# HumRigid1.net
KiCad netlist of a schematic drawn in Altium Designer
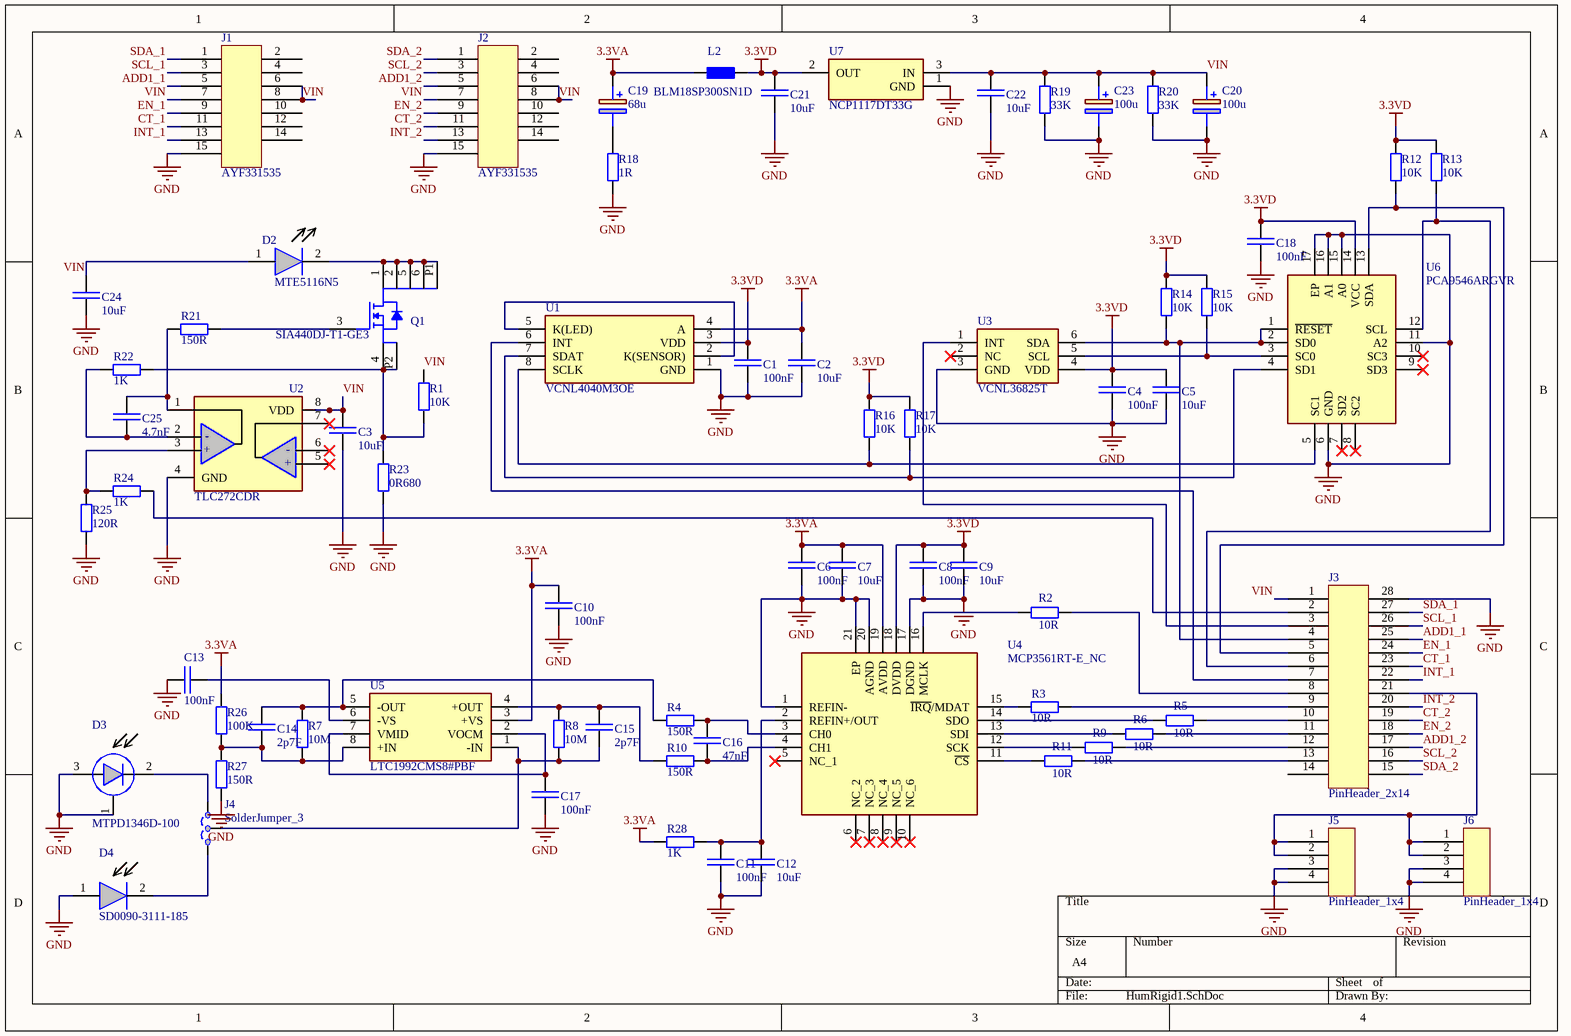
[diagram p0: HumRigid1.SchDoc]

(export (version "E")
  (design (tool "Eeschema 10.0.6"))
  (components
    (comp (ref "C1")
      (value "100nF")
      (footprint "CAP_SM0603_YAGEOCC2_N")
      (description "CAP 100nF SM0603 X7R 50V YAGEO CC2")
      (fields
        (field (name "MANUFACTURER") "Yageo")
        (field (name "MANUFACTURER PART NUMBER") "CC0603KRX7R9BB104")
      )
      (libsource (lib "symbols") (part "CC0603KRX7R9BB104"))
    )
    (comp (ref "C2")
      (value "10uF")
      (footprint "CAP_SM0805_YAGEOCC2_N")
      (description "CAP 10uF SM0805 X5R 16V YAGEO CC2")
      (fields
        (field (name "MANUFACTURER") "Yageo")
        (field (name "MANUFACTURER PART NUMBER") "CC0805KKX7R8BB225")
      )
      (libsource (lib "symbols") (part "CC0805KKX5R8BB106"))
    )
    (comp (ref "C3")
      (value "10uF")
      (footprint "CAP_SM0805_YAGEOCC2_N")
      (description "CAP 10uF SM0805 X5R 16V YAGEO CC2")
      (fields
        (field (name "MANUFACTURER") "Yageo")
        (field (name "MANUFACTURER PART NUMBER") "CC0805KKX7R8BB225")
      )
      (libsource (lib "symbols") (part "CC0805KKX5R8BB106"))
    )
    (comp (ref "C4")
      (value "100nF")
      (footprint "CAP_SM0603_YAGEOCC2_N")
      (description "CAP 100nF SM0603 X7R 50V YAGEO CC2")
      (fields
        (field (name "MANUFACTURER") "Yageo")
        (field (name "MANUFACTURER PART NUMBER") "CC0603KRX7R9BB104")
      )
      (libsource (lib "symbols") (part "CC0603KRX7R9BB104"))
    )
    (comp (ref "C5")
      (value "10uF")
      (footprint "CAP_SM0805_YAGEOCC2_N")
      (description "CAP 10uF SM0805 X5R 16V YAGEO CC2")
      (fields
        (field (name "MANUFACTURER") "Yageo")
        (field (name "MANUFACTURER PART NUMBER") "CC0805KKX7R8BB225")
      )
      (libsource (lib "symbols") (part "CC0805KKX5R8BB106"))
    )
    (comp (ref "C6")
      (value "100nF")
      (footprint "CAP_SM0603_YAGEOCC2_N")
      (description "CAP 100nF SM0603 X7R 50V YAGEO CC2")
      (fields
        (field (name "MANUFACTURER") "Yageo")
        (field (name "MANUFACTURER PART NUMBER") "CC0603KRX7R9BB104")
      )
      (libsource (lib "symbols") (part "CC0603KRX7R9BB104"))
    )
    (comp (ref "C7")
      (value "10uF")
      (footprint "CAP_SM0805_YAGEOCC2_N")
      (description "CAP 10uF SM0805 X5R 16V YAGEO CC2")
      (fields
        (field (name "MANUFACTURER") "Yageo")
        (field (name "MANUFACTURER PART NUMBER") "CC0805KKX7R8BB225")
      )
      (libsource (lib "symbols") (part "CC0805KKX5R8BB106"))
    )
    (comp (ref "C8")
      (value "100nF")
      (footprint "CAP_SM0603_YAGEOCC2_N")
      (description "CAP 100nF SM0603 X7R 50V YAGEO CC2")
      (fields
        (field (name "MANUFACTURER") "Yageo")
        (field (name "MANUFACTURER PART NUMBER") "CC0603KRX7R9BB104")
      )
      (libsource (lib "symbols") (part "CC0603KRX7R9BB104"))
    )
    (comp (ref "C9")
      (value "10uF")
      (footprint "CAP_SM0805_YAGEOCC2_N")
      (description "CAP 10uF SM0805 X5R 16V YAGEO CC2")
      (fields
        (field (name "MANUFACTURER") "Yageo")
        (field (name "MANUFACTURER PART NUMBER") "CC0805KKX7R8BB225")
      )
      (libsource (lib "symbols") (part "CC0805KKX5R8BB106"))
    )
    (comp (ref "C10")
      (value "100nF")
      (footprint "CAP_SM0603_YAGEOCC2_N")
      (description "CAP 100nF SM0603 X7R 50V YAGEO CC2")
      (fields
        (field (name "MANUFACTURER") "Yageo")
        (field (name "MANUFACTURER PART NUMBER") "CC0603KRX7R9BB104")
      )
      (libsource (lib "symbols") (part "CC0603KRX7R9BB104"))
    )
    (comp (ref "C11")
      (value "100nF")
      (footprint "CAP_SM0603_YAGEOCC2_N")
      (description "CAP 100nF SM0603 X7R 50V YAGEO CC2")
      (fields
        (field (name "MANUFACTURER") "Yageo")
        (field (name "MANUFACTURER PART NUMBER") "CC0603KRX7R9BB104")
      )
      (libsource (lib "symbols") (part "CC0603KRX7R9BB104"))
    )
    (comp (ref "C12")
      (value "10uF")
      (footprint "CAP_SM0805_YAGEOCC2_N")
      (description "CAP 10uF SM0805 X5R 16V YAGEO CC2")
      (fields
        (field (name "MANUFACTURER") "Yageo")
        (field (name "MANUFACTURER PART NUMBER") "CC0805KKX7R8BB225")
      )
      (libsource (lib "symbols") (part "CC0805KKX5R8BB106"))
    )
    (comp (ref "C13")
      (value "100nF")
      (footprint "CAP_SM0603_YAGEOCC2_N")
      (description "CAP 100nF SM0603 X7R 50V YAGEO CC2")
      (fields
        (field (name "MANUFACTURER") "Yageo")
        (field (name "MANUFACTURER PART NUMBER") "CC0603KRX7R9BB104")
      )
      (libsource (lib "symbols") (part "CC0603KRX7R9BB104"))
    )
    (comp (ref "C14")
      (value "2p7F")
      (footprint "CAP_SM0603_YAGEOCC2_N")
      (description "CAP 2.7pF (2p7F) SM0603 NPO 50V YAGEO CC2")
      (fields
        (field (name "MANUFACTURER") "Yageo")
        (field (name "MANUFACTURER PART NUMBER") "CC0603CRNPO9BN2R7")
      )
      (libsource (lib "symbols") (part "CC0603CRNPO9BN2R7"))
    )
    (comp (ref "C15")
      (value "2p7F")
      (footprint "CAP_SM0603_YAGEOCC2_N")
      (description "CAP 2.7pF (2p7F) SM0603 NPO 50V YAGEO CC2")
      (fields
        (field (name "MANUFACTURER") "Yageo")
        (field (name "MANUFACTURER PART NUMBER") "CC0603CRNPO9BN2R7")
      )
      (libsource (lib "symbols") (part "CC0603CRNPO9BN2R7"))
    )
    (comp (ref "C16")
      (value "47nF")
      (footprint "CAP_SM0603_YAGEOCC2_N")
      (description "CAP 47nF SM0603 X7R 50V YAGEO CC2")
      (fields
        (field (name "MANUFACTURER") "Yageo")
        (field (name "MANUFACTURER PART NUMBER") "CC0603KRX7R9BB223")
      )
      (libsource (lib "symbols") (part "CC0603KRX7R9BB473"))
    )
    (comp (ref "C17")
      (value "100nF")
      (footprint "CAP_SM0603_YAGEOCC2_N")
      (description "CAP 100nF SM0603 X7R 50V YAGEO CC2")
      (fields
        (field (name "MANUFACTURER") "Yageo")
        (field (name "MANUFACTURER PART NUMBER") "CC0603KRX7R9BB104")
      )
      (libsource (lib "symbols") (part "CC0603KRX7R9BB104"))
    )
    (comp (ref "C18")
      (value "100nF")
      (footprint "CAP_SM0603_YAGEOCC2_N")
      (description "CAP 100nF SM0603 X7R 50V YAGEO CC2")
      (fields
        (field (name "MANUFACTURER") "Yageo")
        (field (name "MANUFACTURER PART NUMBER") "CC0603KRX7R9BB104")
      )
      (libsource (lib "symbols") (part "CC0603KRX7R9BB104"))
    )
    (comp (ref "C19")
      (value "68u")
      (footprint "CAPAE660X770N")
      (fields
        (field (name "MOUSER PART NUMBER") "710-865080545012")
        (field (name "MANUFACTURER_PART_NUMBER") "865080545012")
      )
      (libsource (lib "symbols") (part "865080545011"))
    )
    (comp (ref "C20")
      (value "100u")
      (footprint "CAPAE660X770N")
      (fields
        (field (name "MOUSER PART NUMBER") "710-865080545012")
        (field (name "MANUFACTURER_PART_NUMBER") "865080545012")
      )
      (libsource (lib "symbols") (part "865080545012"))
    )
    (comp (ref "C21")
      (value "10uF")
      (footprint "CAP_SM0805_YAGEOCC2_N")
      (description "CAP 10uF SM0805 X5R 16V YAGEO CC2")
      (fields
        (field (name "MANUFACTURER") "Yageo")
        (field (name "MANUFACTURER PART NUMBER") "CC0805KKX7R8BB225")
      )
      (libsource (lib "symbols") (part "CC0805KKX5R8BB106"))
    )
    (comp (ref "C22")
      (value "10uF")
      (footprint "CAP_SM0805_YAGEOCC2_N")
      (description "CAP 10uF SM0805 X5R 16V YAGEO CC2")
      (fields
        (field (name "MANUFACTURER") "Yageo")
        (field (name "MANUFACTURER PART NUMBER") "CC0805KKX7R8BB225")
      )
      (libsource (lib "symbols") (part "CC0805KKX5R8BB106"))
    )
    (comp (ref "C23")
      (value "100u")
      (footprint "CAPAE660X770N")
      (fields
        (field (name "MOUSER PART NUMBER") "710-865080545012")
        (field (name "MANUFACTURER_PART_NUMBER") "865080545012")
      )
      (libsource (lib "symbols") (part "865080545012"))
    )
    (comp (ref "C24")
      (value "10uF")
      (footprint "CAP_SM0805_YAGEOCC2_N")
      (description "CAP 10uF SM0805 X5R 16V YAGEO CC2")
      (fields
        (field (name "MANUFACTURER") "Yageo")
        (field (name "MANUFACTURER PART NUMBER") "CC0805KKX7R8BB225")
      )
      (libsource (lib "symbols") (part "CC0805KKX5R8BB106"))
    )
    (comp (ref "C25")
      (value "4.7nF")
      (footprint "CAP_SM0603_YAGEOCC2_N")
      (description "CAP 4.7nF SM0603 X7R 50V YAGEO CC2")
      (fields
        (field (name "MANUFACTURER") "Yageo")
        (field (name "MANUFACTURER PART NUMBER") "CC0603KRX7R9BB223")
      )
      (libsource (lib "symbols") (part "CC0603KRX7R9BB472"))
    )
    (comp (ref "D2")
      (value "MTE5116N5")
      (footprint "MTE5116N5")
      (description "MTE5116N5 SWIR Infrared Emitter 1650nm")
      (libsource (lib "symbols") (part "MTE5116N5"))
    )
    (comp (ref "D3")
      (value "MTPD1346D-100")
      (footprint "MTPD1346D100")
      (description "MTPD1346D-100 High Speed InGaAs PIN Photodiode 600-1750nm")
      (libsource (lib "symbols") (part "MTPD1346D-100"))
    )
    (comp (ref "D4")
      (value "SD0090-3111-185")
      (footprint "SD00903111185")
      (description "SD0090-3111-185 SMD InGaAs Photodiode 900-1650nm")
      (libsource (lib "symbols") (part "SD0090-3111-185"))
    )
    (comp (ref "J1")
      (value "AYF331535")
      (footprint "AYF331535")
      (description "AYF331535 FFC & FPC-Steckverbinder CONNECTOR SURFACE MOUNT")
      (libsource (lib "Base_Symbols") (part "AYF331535"))
    )
    (comp (ref "J2")
      (value "AYF331535")
      (footprint "AYF331535")
      (description "AYF331535 FFC & FPC-Steckverbinder CONNECTOR SURFACE MOUNT")
      (libsource (lib "Base_Symbols") (part "AYF331535"))
    )
    (comp (ref "J3")
      (value "PinHeader_2x14")
      (footprint "PinHeader_2x14_2.54mm")
      (description "PinHeader_2x14 2.54mm Pitch")
      (libsource (lib "symbols") (part "PinHeader_2x14_2.54mm_1"))
    )
    (comp (ref "J4")
      (value "SolderJumper_3")
      (footprint "SolderJumper3_1")
      (libsource (lib "symbols") (part "SolderJumper_3"))
    )
    (comp (ref "J5")
      (value "PinHeader_1x4")
      (footprint "PinHeader_1x4_2.54mm")
      (description "PinHeader_1x4 2.54mm Pitch")
      (libsource (lib "symbols") (part "PinHeader_1x4_2.54mm"))
    )
    (comp (ref "J6")
      (value "PinHeader_1x4")
      (footprint "PinHeader_1x4_2.54mm")
      (description "PinHeader_1x4 2.54mm Pitch")
      (libsource (lib "symbols") (part "PinHeader_1x4_2.54mm"))
    )
    (comp (ref "L2")
      (value "BLM18SP300SN1D")
      (footprint "Chip2PinSM127P600-8N")
      (description "Ferrite Beads 0603 30ohm 10% 6A")
      (fields (field (name "MOUSER PART NUMBER") "81-BLM18SP300SN1D"))
      (libsource (lib "symbols") (part "BLM18SP300SN1D"))
    )
    (comp (ref "Q1")
      (value "SIA440DJ-T1-GE3")
      (footprint "SIA440DJT1GE3")
      (description "MOSFET 40V Vds 12V Vgs PowerPAK SC-70")
      (fields (field (name "MOUSER PART NUMBER") "78-SIA440DJ-T1-GE3"))
      (libsource (lib "symbols") (part "SIA440DJ-T1-GE3"))
    )
    (comp (ref "R1")
      (value "10K")
      (footprint "RES_SM0603_YAGEORC_N")
      (description "RES 10K SM0603 YAGEO RC_L")
      (fields
        (field (name "MANUFACTURER") "Yageo")
        (field (name "MANUFACTURER PART NUMBER") "RC0603FR-0710KL")
      )
      (libsource (lib "symbols") (part "RC0603FR-0710KL"))
    )
    (comp (ref "R2")
      (value "10R")
      (footprint "RES_SM0603_YAGEORC_N")
      (description "RES 10R SM0603 YAGEO RC_L")
      (fields
        (field (name "MANUFACTURER") "Yageo")
        (field (name "MANUFACTURER PART NUMBER") "RC0603FR-0710RL")
      )
      (libsource (lib "symbols") (part "RC0603FR-0710RL"))
    )
    (comp (ref "R3")
      (value "10R")
      (footprint "RES_SM0603_YAGEORC_N")
      (description "RES 10R SM0603 YAGEO RC_L")
      (fields
        (field (name "MANUFACTURER") "Yageo")
        (field (name "MANUFACTURER PART NUMBER") "RC0603FR-0710RL")
      )
      (libsource (lib "symbols") (part "RC0603FR-0710RL"))
    )
    (comp (ref "R4")
      (value "150R")
      (footprint "RES_SM0603_YAGEORC_N")
      (description "RES 150R SM0603 YAGEO RC_L")
      (fields
        (field (name "MANUFACTURER") "Yageo")
        (field (name "MANUFACTURER PART NUMBER") "RC0603FR-07150RL")
      )
      (libsource (lib "symbols") (part "RC0603FR-07150RL"))
    )
    (comp (ref "R5")
      (value "10R")
      (footprint "RES_SM0603_YAGEORC_N")
      (description "RES 10R SM0603 YAGEO RC_L")
      (fields
        (field (name "MANUFACTURER") "Yageo")
        (field (name "MANUFACTURER PART NUMBER") "RC0603FR-0710RL")
      )
      (libsource (lib "symbols") (part "RC0603FR-0710RL"))
    )
    (comp (ref "R6")
      (value "10R")
      (footprint "RES_SM0603_YAGEORC_N")
      (description "RES 10R SM0603 YAGEO RC_L")
      (fields
        (field (name "MANUFACTURER") "Yageo")
        (field (name "MANUFACTURER PART NUMBER") "RC0603FR-0710RL")
      )
      (libsource (lib "symbols") (part "RC0603FR-0710RL"))
    )
    (comp (ref "R7")
      (value "10M")
      (footprint "RES_SM0603_YAGEORC_N")
      (description "RES 10M SM0603 YAGEO RC_L")
      (fields
        (field (name "MANUFACTURER") "Yageo")
        (field (name "MANUFACTURER PART NUMBER") "RC0603FR-0710ML")
      )
      (libsource (lib "symbols") (part "RC0603FR-0710ML"))
    )
    (comp (ref "R8")
      (value "10M")
      (footprint "RES_SM0603_YAGEORC_N")
      (description "RES 10M SM0603 YAGEO RC_L")
      (fields
        (field (name "MANUFACTURER") "Yageo")
        (field (name "MANUFACTURER PART NUMBER") "RC0603FR-0710ML")
      )
      (libsource (lib "symbols") (part "RC0603FR-0710ML"))
    )
    (comp (ref "R9")
      (value "10R")
      (footprint "RES_SM0603_YAGEORC_N")
      (description "RES 10R SM0603 YAGEO RC_L")
      (fields
        (field (name "MANUFACTURER") "Yageo")
        (field (name "MANUFACTURER PART NUMBER") "RC0603FR-0710RL")
      )
      (libsource (lib "symbols") (part "RC0603FR-0710RL"))
    )
    (comp (ref "R10")
      (value "150R")
      (footprint "RES_SM0603_YAGEORC_N")
      (description "RES 150R SM0603 YAGEO RC_L")
      (fields
        (field (name "MANUFACTURER") "Yageo")
        (field (name "MANUFACTURER PART NUMBER") "RC0603FR-07150RL")
      )
      (libsource (lib "symbols") (part "RC0603FR-07150RL"))
    )
    (comp (ref "R11")
      (value "10R")
      (footprint "RES_SM0603_YAGEORC_N")
      (description "RES 10R SM0603 YAGEO RC_L")
      (fields
        (field (name "MANUFACTURER") "Yageo")
        (field (name "MANUFACTURER PART NUMBER") "RC0603FR-0710RL")
      )
      (libsource (lib "symbols") (part "RC0603FR-0710RL"))
    )
    (comp (ref "R12")
      (value "10K")
      (footprint "RES_SM0603_YAGEORC_N")
      (description "RES 10K SM0603 YAGEO RC_L")
      (fields
        (field (name "MANUFACTURER") "Yageo")
        (field (name "MANUFACTURER PART NUMBER") "RC0603FR-0710KL")
      )
      (libsource (lib "symbols") (part "RC0603FR-0710KL"))
    )
    (comp (ref "R13")
      (value "10K")
      (footprint "RES_SM0603_YAGEORC_N")
      (description "RES 10K SM0603 YAGEO RC_L")
      (fields
        (field (name "MANUFACTURER") "Yageo")
        (field (name "MANUFACTURER PART NUMBER") "RC0603FR-0710KL")
      )
      (libsource (lib "symbols") (part "RC0603FR-0710KL"))
    )
    (comp (ref "R14")
      (value "10K")
      (footprint "RES_SM0603_YAGEORC_N")
      (description "RES 10K SM0603 YAGEO RC_L")
      (fields
        (field (name "MANUFACTURER") "Yageo")
        (field (name "MANUFACTURER PART NUMBER") "RC0603FR-0710KL")
      )
      (libsource (lib "symbols") (part "RC0603FR-0710KL"))
    )
    (comp (ref "R15")
      (value "10K")
      (footprint "RES_SM0603_YAGEORC_N")
      (description "RES 10K SM0603 YAGEO RC_L")
      (fields
        (field (name "MANUFACTURER") "Yageo")
        (field (name "MANUFACTURER PART NUMBER") "RC0603FR-0710KL")
      )
      (libsource (lib "symbols") (part "RC0603FR-0710KL"))
    )
    (comp (ref "R16")
      (value "10K")
      (footprint "RES_SM0603_YAGEORC_N")
      (description "RES 10K SM0603 YAGEO RC_L")
      (fields
        (field (name "MANUFACTURER") "Yageo")
        (field (name "MANUFACTURER PART NUMBER") "RC0603FR-0710KL")
      )
      (libsource (lib "symbols") (part "RC0603FR-0710KL"))
    )
    (comp (ref "R17")
      (value "10K")
      (footprint "RES_SM0603_YAGEORC_N")
      (description "RES 10K SM0603 YAGEO RC_L")
      (fields
        (field (name "MANUFACTURER") "Yageo")
        (field (name "MANUFACTURER PART NUMBER") "RC0603FR-0710KL")
      )
      (libsource (lib "symbols") (part "RC0603FR-0710KL"))
    )
    (comp (ref "R18")
      (value "1R")
      (footprint "RES_SM0603_YAGEORC_N")
      (description "RES 1R SM0603YAGEO RC_L")
      (fields
        (field (name "MANUFACTURER") "Yageo")
        (field (name "MANUFACTURER PART NUMBER") "RC0805FR-0710RL")
      )
      (libsource (lib "symbols") (part "RC0603FR-071RL"))
    )
    (comp (ref "R19")
      (value "33K")
      (footprint "RES_SM0603_YAGEORC_N")
      (description "RES 33K SM0603 YAGEO RC_L")
      (fields
        (field (name "MANUFACTURER") "Yageo")
        (field (name "MANUFACTURER PART NUMBER") "RC0603FR-0733KL")
      )
      (libsource (lib "symbols") (part "RC0603FR-0733KL"))
    )
    (comp (ref "R20")
      (value "33K")
      (footprint "RES_SM0603_YAGEORC_N")
      (description "RES 33K SM0603 YAGEO RC_L")
      (fields
        (field (name "MANUFACTURER") "Yageo")
        (field (name "MANUFACTURER PART NUMBER") "RC0603FR-0733KL")
      )
      (libsource (lib "symbols") (part "RC0603FR-0733KL"))
    )
    (comp (ref "R21")
      (value "150R")
      (footprint "RES_SM0603_YAGEORC_N")
      (description "RES 150R SM0603 YAGEO RC_L")
      (fields
        (field (name "MANUFACTURER") "Yageo")
        (field (name "MANUFACTURER PART NUMBER") "RC0603FR-07150RL")
      )
      (libsource (lib "symbols") (part "RC0603FR-07150RL"))
    )
    (comp (ref "R22")
      (value "1K")
      (footprint "RES_SM0603_YAGEORC_N")
      (description "RES 1K SM0603 YAGEO RC_L")
      (fields
        (field (name "MANUFACTURER") "Yageo")
        (field (name "MANUFACTURER PART NUMBER") "RC0603FR-071KL")
      )
      (libsource (lib "symbols") (part "RC0603FR-071KL"))
    )
    (comp (ref "R23")
      (value "0R680")
      (footprint "MFLA1206")
      (description "RES 0R680 SM1206 Eaton 500mW")
      (fields
        (field (name "MANUFACTURER") "Yageo")
        (field (name "MANUFACTURER PART NUMBER") "RC0603FR-07150RL")
      )
      (libsource (lib "symbols") (part "MFLA1206R6800FS"))
    )
    (comp (ref "R24")
      (value "1K")
      (footprint "RES_SM0603_YAGEORC_N")
      (description "RES 1K SM0603 YAGEO RC_L")
      (fields
        (field (name "MANUFACTURER") "Yageo")
        (field (name "MANUFACTURER PART NUMBER") "RC0603FR-071KL")
      )
      (libsource (lib "symbols") (part "RC0603FR-071KL"))
    )
    (comp (ref "R25")
      (value "120R")
      (footprint "RES_SM0603_YAGEORC_N")
      (description "RES 120R SM0603 YAGEO RC_L")
      (fields
        (field (name "MANUFACTURER") "Yageo")
        (field (name "MANUFACTURER PART NUMBER") "RC0603FR-07120RL")
      )
      (libsource (lib "symbols") (part "RC0603FR-07120RL"))
    )
    (comp (ref "R26")
      (value "100K")
      (footprint "RES_SM0603_YAGEORC_N")
      (description "RES 100K SM0603 YAGEO RC_L")
      (fields
        (field (name "MANUFACTURER") "Yageo")
        (field (name "MANUFACTURER PART NUMBER") "RC0603FR-13100KL")
      )
      (libsource (lib "symbols") (part "RC0603FR-13100KL"))
    )
    (comp (ref "R27")
      (value "150R")
      (footprint "RES_SM0603_YAGEORC_N")
      (description "RES 150R SM0603 YAGEO RC_L")
      (fields
        (field (name "MANUFACTURER") "Yageo")
        (field (name "MANUFACTURER PART NUMBER") "RC0603FR-07150RL")
      )
      (libsource (lib "") (part "RC0603FR-07150RL_1"))
    )
    (comp (ref "R28")
      (value "1K")
      (footprint "RES_SM0603_YAGEORC_N")
      (description "RES 1K SM0603 YAGEO RC_L")
      (fields
        (field (name "MANUFACTURER") "Yageo")
        (field (name "MANUFACTURER PART NUMBER") "RC0603FR-071KL")
      )
      (libsource (lib "symbols") (part "RC0603FR-071KL"))
    )
    (comp (ref "U1")
      (value "VCNL4040M3OE")
      (footprint "VCNL4040M3OE")
      (fields (field (name "MOUSER PART NUMBER") "78-VCNL4040M3OE"))
      (libsource (lib "symbols") (part "VCNL4040M3OE"))
    )
    (comp (ref "U2")
      (value "TLC272CDR")
      (footprint "SOIC127P600X175-8N")
      (description "TLC272CDRG4, Dual Operational Amplifier 1.7MHz CMOS 5 to 15V, 8-Pin SOIC")
      (fields (field (name "MOUSER PART NUMBER") "595-TLC272CDR"))
      (libsource (lib "symbols") (part "TLC272CDR"))
    )
    (comp (ref "U3")
      (value "VCNL36825T")
      (footprint "VCNL36825T")
      (description "Proximity Sensors PROX SENS INTER VCSEL I2C-E4, IC SENSORS")
      (fields (field (name "MOUSER PART NUMBER") "78-VCNL36825T"))
      (libsource (lib "symbols") (part "VCNL36825T"))
    )
    (comp (ref "U4")
      (value "MCP3561RT-E_NC")
      (footprint "QFN40P300X300X60-21N-D")
      (description "Microchip, 24 bit- ADC 153.6ksps, 20-Pin UQFN")
      (fields
        (field (name "MOUSER PART NUMBER") "579-MCP3561RT-E/NC")
        (field (name "MANUFACTURER_PART_NUMBER") "MCP3561RT-E/NC")
      )
      (libsource (lib "symbols") (part "MCP3561RT-E_NC"))
    )
    (comp (ref "U5")
      (value "LTC1992CMS8#PBF")
      (footprint "SOP65P490X110-8N")
      (description "LTC1992CMS8#PBF Analog Devices, Differential Amplifier 3MHz Rail to Rail Output 8-Pin MSOP")
      (fields (field (name "MOUSER PART NUMBER") "584-LTC1992CMS8#PBF"))
      (libsource (lib "symbols") (part "LTC1992CMS8#PBF"))
    )
    (comp (ref "U6")
      (value "PCA9546ARGVR")
      (footprint "QFN65P400X400X100-17N-D")
      (description "4-Channel I2C And SMBus Switch With Reset Functions")
      (fields (field (name "MOUSER PART NUMBER") "595-PCA9546ARGVR"))
      (libsource (lib "symbols") (part "PCA9546ARGVR"))
    )
    (comp (ref "U7")
      (value "NCP1117DT33G")
      (footprint "NCP1117DT33G")
      (description "Linear Voltage Regulator IC Positive Fixed 1 Output 1A DPAK")
      (fields (field (name "MOUSER PART NUMBER") "863-NCP1117DT33G"))
      (libsource (lib "symbols") (part "NCP1117DT33G"))
    )
  )
  (nets
    (net (code "1") (name "/ADD1_1") (class "Default")
      (node (ref "J1") (pin "5") (pintype "passive"))
      (node (ref "J3") (pin "25") (pintype "passive"))
    )
    (net (code "2") (name "/ADD1_2") (class "Default")
      (node (ref "J2") (pin "5") (pintype "passive"))
      (node (ref "J3") (pin "17") (pintype "passive"))
    )
    (net (code "3") (name "/CT_1") (class "Default")
      (node (ref "J1") (pin "11") (pintype "passive"))
      (node (ref "J3") (pin "23") (pintype "passive"))
    )
    (net (code "4") (name "/CT_2") (class "Default")
      (node (ref "J2") (pin "11") (pintype "passive"))
      (node (ref "J3") (pin "19") (pintype "passive"))
    )
    (net (code "5") (name "/EN_1") (class "Default")
      (node (ref "J1") (pin "9") (pintype "passive"))
      (node (ref "J3") (pin "24") (pintype "passive"))
    )
    (net (code "6") (name "/EN_2") (class "Default")
      (node (ref "J2") (pin "9") (pintype "passive"))
      (node (ref "J3") (pin "18") (pintype "passive"))
    )
    (net (code "7") (name "/INT_1") (class "Default")
      (node (ref "J1") (pin "13") (pintype "passive"))
      (node (ref "J3") (pin "22") (pintype "passive"))
    )
    (net (code "8") (name "/INT_2") (class "Default")
      (node (ref "J2") (pin "13") (pintype "passive"))
      (node (ref "J3") (pin "20") (pintype "passive"))
    )
    (net (code "9") (name "/SCL_1") (class "Default")
      (node (ref "J1") (pin "3") (pintype "passive"))
      (node (ref "J3") (pin "26") (pintype "passive"))
    )
    (net (code "10") (name "/SCL_2") (class "Default")
      (node (ref "J2") (pin "3") (pintype "passive"))
      (node (ref "J3") (pin "16") (pintype "passive"))
    )
    (net (code "11") (name "/SDA_1") (class "Default")
      (node (ref "J1") (pin "1") (pintype "passive"))
      (node (ref "J3") (pin "27") (pintype "passive"))
    )
    (net (code "12") (name "/SDA_2") (class "Default")
      (node (ref "J2") (pin "1") (pintype "passive"))
      (node (ref "J3") (pin "15") (pintype "passive"))
    )
    (net (code "13") (name "/VIN") (class "Default")
      (node (ref "C20") (pin "1") (pinfunction "+_1") (pintype "passive"))
      (node (ref "C22") (pin "2") (pintype "passive"))
      (node (ref "C23") (pin "1") (pinfunction "+_1") (pintype "passive"))
      (node (ref "C24") (pin "1") (pintype "passive"))
      (node (ref "C3") (pin "1") (pintype "passive"))
      (node (ref "D2") (pin "1") (pinfunction "Anode_1") (pintype "passive"))
      (node (ref "J1") (pin "6") (pintype "passive"))
      (node (ref "J1") (pin "7") (pintype "passive"))
      (node (ref "J1") (pin "8") (pintype "passive"))
      (node (ref "J2") (pin "6") (pintype "passive"))
      (node (ref "J2") (pin "7") (pintype "passive"))
      (node (ref "J2") (pin "8") (pintype "passive"))
      (node (ref "J3") (pin "1") (pintype "passive"))
      (node (ref "R1") (pin "2") (pintype "passive"))
      (node (ref "R19") (pin "2") (pintype "passive"))
      (node (ref "R20") (pin "2") (pintype "passive"))
      (node (ref "U2") (pin "8") (pinfunction "VDD_8") (pintype "passive"))
      (node (ref "U7") (pin "3") (pinfunction "IN_3") (pintype "passive"))
    )
    (net (code "14") (name "3.3VA") (class "Default")
      (node (ref "C10") (pin "1") (pintype "passive"))
      (node (ref "C19") (pin "1") (pinfunction "+_1") (pintype "passive"))
      (node (ref "C2") (pin "1") (pintype "passive"))
      (node (ref "C6") (pin "2") (pintype "passive"))
      (node (ref "C7") (pin "2") (pintype "passive"))
      (node (ref "L2") (pin "1") (pintype "passive"))
      (node (ref "R26") (pin "2") (pintype "passive"))
      (node (ref "R28") (pin "1") (pintype "passive"))
      (node (ref "U1") (pin "4") (pinfunction "A_4") (pintype "passive"))
      (node (ref "U4") (pin "19") (pinfunction "AVDD_19") (pintype "passive"))
      (node (ref "U5") (pin "3") (pinfunction "+VS_3") (pintype "passive"))
    )
    (net (code "15") (name "3.3VD") (class "Default")
      (node (ref "C1") (pin "1") (pintype "passive"))
      (node (ref "C18") (pin "2") (pintype "passive"))
      (node (ref "C21") (pin "2") (pintype "passive"))
      (node (ref "C4") (pin "1") (pintype "passive"))
      (node (ref "C5") (pin "1") (pintype "passive"))
      (node (ref "C8") (pin "2") (pintype "passive"))
      (node (ref "C9") (pin "2") (pintype "passive"))
      (node (ref "L2") (pin "2") (pintype "passive"))
      (node (ref "R12") (pin "2") (pintype "passive"))
      (node (ref "R13") (pin "2") (pintype "passive"))
      (node (ref "R14") (pin "2") (pintype "passive"))
      (node (ref "R15") (pin "2") (pintype "passive"))
      (node (ref "R16") (pin "2") (pintype "passive"))
      (node (ref "R17") (pin "2") (pintype "passive"))
      (node (ref "U1") (pin "3") (pinfunction "VDD_3") (pintype "passive"))
      (node (ref "U3") (pin "4") (pinfunction "VDD_4") (pintype "passive"))
      (node (ref "U4") (pin "18") (pinfunction "DVDD_18") (pintype "passive"))
      (node (ref "U6") (pin "14") (pinfunction "VCC_14") (pintype "passive"))
      (node (ref "U7") (pin "2") (pinfunction "OUT_2") (pintype "passive"))
    )
    (net (code "16") (name "GND") (class "Default")
      (node (ref "C1") (pin "2") (pintype "passive"))
      (node (ref "C10") (pin "2") (pintype "passive"))
      (node (ref "C11") (pin "2") (pintype "passive"))
      (node (ref "C12") (pin "2") (pintype "passive"))
      (node (ref "C13") (pin "2") (pintype "passive"))
      (node (ref "C17") (pin "2") (pintype "passive"))
      (node (ref "C18") (pin "1") (pintype "passive"))
      (node (ref "C2") (pin "2") (pintype "passive"))
      (node (ref "C20") (pin "2") (pinfunction "-_2") (pintype "passive"))
      (node (ref "C21") (pin "1") (pintype "passive"))
      (node (ref "C22") (pin "1") (pintype "passive"))
      (node (ref "C23") (pin "2") (pinfunction "-_2") (pintype "passive"))
      (node (ref "C24") (pin "2") (pintype "passive"))
      (node (ref "C3") (pin "2") (pintype "passive"))
      (node (ref "C4") (pin "2") (pintype "passive"))
      (node (ref "C5") (pin "2") (pintype "passive"))
      (node (ref "C6") (pin "1") (pintype "passive"))
      (node (ref "C7") (pin "1") (pintype "passive"))
      (node (ref "C8") (pin "1") (pintype "passive"))
      (node (ref "C9") (pin "1") (pintype "passive"))
      (node (ref "D3") (pin "1") (pinfunction "Case_1") (pintype "passive"))
      (node (ref "D3") (pin "3") (pinfunction "Anode_3") (pintype "passive"))
      (node (ref "D4") (pin "1") (pinfunction "Anode_1") (pintype "passive"))
      (node (ref "J1") (pin "15") (pintype "passive"))
      (node (ref "J2") (pin "15") (pintype "passive"))
      (node (ref "J3") (pin "28") (pintype "passive"))
      (node (ref "J5") (pin "3") (pintype "passive"))
      (node (ref "J5") (pin "4") (pintype "passive"))
      (node (ref "J6") (pin "3") (pintype "passive"))
      (node (ref "J6") (pin "4") (pintype "passive"))
      (node (ref "R18") (pin "1") (pintype "passive"))
      (node (ref "R19") (pin "1") (pintype "passive"))
      (node (ref "R20") (pin "1") (pintype "passive"))
      (node (ref "R23") (pin "1") (pintype "passive"))
      (node (ref "R25") (pin "1") (pintype "passive"))
      (node (ref "R27") (pin "1") (pintype "passive"))
      (node (ref "U1") (pin "1") (pinfunction "GND_1") (pintype "passive"))
      (node (ref "U2") (pin "4") (pinfunction "GND_4") (pintype "passive"))
      (node (ref "U3") (pin "3") (pinfunction "GND_3") (pintype "passive"))
      (node (ref "U4") (pin "1") (pinfunction "REFIN-_1") (pintype "passive"))
      (node (ref "U4") (pin "17") (pinfunction "DGND_17") (pintype "passive"))
      (node (ref "U4") (pin "20") (pinfunction "AGND_20") (pintype "passive"))
      (node (ref "U4") (pin "21") (pinfunction "EP_21") (pintype "passive"))
      (node (ref "U6") (pin "11") (pinfunction "A2_11") (pintype "passive"))
      (node (ref "U6") (pin "15") (pinfunction "A0_15") (pintype "passive"))
      (node (ref "U6") (pin "16") (pinfunction "A1_16") (pintype "passive"))
      (node (ref "U6") (pin "17") (pinfunction "EP_17") (pintype "passive"))
      (node (ref "U6") (pin "6") (pinfunction "GND_6") (pintype "passive"))
      (node (ref "U7") (pin "1") (pinfunction "GND_1") (pintype "passive"))
    )
    (net (code "17") (name "Net-(C19--)") (class "Default")
      (node (ref "C19") (pin "2") (pinfunction "-_2") (pintype "passive"))
      (node (ref "R18") (pin "2") (pintype "passive"))
    )
    (net (code "18") (name "Net-(D2-Cathode)") (class "Default")
      (node (ref "D2") (pin "2") (pinfunction "Cathode_2") (pintype "passive"))
      (node (ref "Q1") (pin "1") (pinfunction "D_1") (pintype "passive"))
      (node (ref "Q1") (pin "2") (pinfunction "D_2") (pintype "passive"))
      (node (ref "Q1") (pin "5") (pinfunction "D_5") (pintype "passive"))
      (node (ref "Q1") (pin "6") (pinfunction "D_6") (pintype "passive"))
      (node (ref "Q1") (pin "P1") (pinfunction "D_P1") (pintype "passive"))
    )
    (net (code "19") (name "Net-(D3-Cathode)") (class "Default")
      (node (ref "D3") (pin "2") (pinfunction "Cathode_2") (pintype "passive"))
      (node (ref "J4") (pin "2") (pintype "passive"))
    )
    (net (code "20") (name "Net-(D4-Cathode)") (class "Default")
      (node (ref "D4") (pin "2") (pinfunction "Cathode_2") (pintype "passive"))
      (node (ref "J4") (pin "3") (pintype "passive"))
    )
    (net (code "21") (name "Net-(J3-Pad2)") (class "Default")
      (node (ref "J3") (pin "2") (pintype "passive"))
      (node (ref "R24") (pin "2") (pintype "passive"))
    )
    (net (code "22") (name "Net-(J3-Pad8)") (class "Default")
      (node (ref "J3") (pin "8") (pintype "passive"))
      (node (ref "R2") (pin "2") (pintype "passive"))
    )
    (net (code "23") (name "Net-(J3-Pad9)") (class "Default")
      (node (ref "J3") (pin "9") (pintype "passive"))
      (node (ref "R3") (pin "2") (pintype "passive"))
    )
    (net (code "24") (name "Net-(J3-Pad10)") (class "Default")
      (node (ref "J3") (pin "10") (pintype "passive"))
      (node (ref "R5") (pin "2") (pintype "passive"))
    )
    (net (code "25") (name "Net-(J3-Pad11)") (class "Default")
      (node (ref "J3") (pin "11") (pintype "passive"))
      (node (ref "R6") (pin "2") (pintype "passive"))
    )
    (net (code "26") (name "Net-(J3-Pad12)") (class "Default")
      (node (ref "J3") (pin "12") (pintype "passive"))
      (node (ref "R9") (pin "2") (pintype "passive"))
    )
    (net (code "27") (name "Net-(J3-Pad13)") (class "Default")
      (node (ref "J3") (pin "13") (pintype "passive"))
      (node (ref "R11") (pin "2") (pintype "passive"))
    )
    (net (code "28") (name "Net-(J3-Pad21)") (class "Default")
      (node (ref "J3") (pin "21") (pintype "passive"))
      (node (ref "J5") (pin "1") (pintype "passive"))
      (node (ref "J5") (pin "2") (pintype "passive"))
      (node (ref "J6") (pin "1") (pintype "passive"))
      (node (ref "J6") (pin "2") (pintype "passive"))
    )
    (net (code "29") (name "Net-(Q1-G)") (class "Default")
      (node (ref "Q1") (pin "3") (pinfunction "G_3") (pintype "passive"))
      (node (ref "R21") (pin "2") (pintype "passive"))
    )
    (net (code "30") (name "Net-(Q1-S-Pad4)") (class "Default")
      (node (ref "Q1") (pin "4") (pinfunction "S_4") (pintype "passive"))
      (node (ref "Q1") (pin "P2") (pinfunction "S_P2") (pintype "passive"))
      (node (ref "R1") (pin "1") (pintype "passive"))
      (node (ref "R22") (pin "2") (pintype "passive"))
      (node (ref "R23") (pin "2") (pintype "passive"))
    )
    (net (code "31") (name "Net-(U1-INT)") (class "Default")
      (node (ref "J3") (pin "7") (pintype "passive"))
      (node (ref "U1") (pin "6") (pinfunction "INT_6") (pintype "passive"))
    )
    (net (code "32") (name "Net-(U1-K(LED))") (class "Default")
      (node (ref "U1") (pin "2") (pinfunction "K(SENSOR)_2") (pintype "passive"))
      (node (ref "U1") (pin "5") (pinfunction "K(LED)_5") (pintype "passive"))
    )
    (net (code "33") (name "Net-(U1-SCLK)") (class "Default")
      (node (ref "R16") (pin "1") (pintype "passive"))
      (node (ref "U1") (pin "8") (pinfunction "SCLK_8") (pintype "passive"))
      (node (ref "U6") (pin "5") (pinfunction "SC1_5") (pintype "passive"))
    )
    (net (code "34") (name "Net-(U1-SDAT)") (class "Default")
      (node (ref "R17") (pin "1") (pintype "passive"))
      (node (ref "U1") (pin "7") (pinfunction "SDAT_7") (pintype "passive"))
      (node (ref "U6") (pin "4") (pinfunction "SD1_4") (pintype "passive"))
    )
    (net (code "35") (name "Net-(U2-1IN+)") (class "Default")
      (node (ref "R24") (pin "1") (pintype "passive"))
      (node (ref "R25") (pin "2") (pintype "passive"))
      (node (ref "U2") (pin "3") (pinfunction "1IN+_3") (pintype "passive"))
    )
    (net (code "36") (name "Net-(U2-1IN-)") (class "Default")
      (node (ref "C25") (pin "1") (pintype "passive"))
      (node (ref "R22") (pin "1") (pintype "passive"))
      (node (ref "U2") (pin "2") (pinfunction "1IN-_2") (pintype "passive"))
    )
    (net (code "37") (name "Net-(U2-1OUT)") (class "Default")
      (node (ref "C25") (pin "2") (pintype "passive"))
      (node (ref "R21") (pin "1") (pintype "passive"))
      (node (ref "U2") (pin "1") (pinfunction "1OUT_1") (pintype "passive"))
    )
    (net (code "38") (name "Net-(U3-INT)") (class "Default")
      (node (ref "J3") (pin "3") (pintype "passive"))
      (node (ref "U3") (pin "1") (pinfunction "INT_1") (pintype "passive"))
    )
    (net (code "39") (name "Net-(U3-SCL)") (class "Default")
      (node (ref "R15") (pin "1") (pintype "passive"))
      (node (ref "U3") (pin "5") (pinfunction "SCL_5") (pintype "passive"))
      (node (ref "U6") (pin "3") (pinfunction "SC0_3") (pintype "passive"))
    )
    (net (code "40") (name "Net-(U3-SDA)") (class "Default")
      (node (ref "J3") (pin "4") (pintype "passive"))
      (node (ref "R14") (pin "1") (pintype "passive"))
      (node (ref "U3") (pin "6") (pinfunction "SDA_6") (pintype "passive"))
      (node (ref "U6") (pin "1") (pinfunction "~{RESET}_1") (pintype "passive"))
      (node (ref "U6") (pin "2") (pinfunction "SD0_2") (pintype "passive"))
    )
    (net (code "41") (name "Net-(U4-CH0)") (class "Default")
      (node (ref "C16") (pin "1") (pintype "passive"))
      (node (ref "R4") (pin "2") (pintype "passive"))
      (node (ref "U4") (pin "3") (pinfunction "CH0_3") (pintype "passive"))
    )
    (net (code "42") (name "Net-(U4-CH1)") (class "Default")
      (node (ref "C16") (pin "2") (pintype "passive"))
      (node (ref "R10") (pin "2") (pintype "passive"))
      (node (ref "U4") (pin "4") (pinfunction "CH1_4") (pintype "passive"))
    )
    (net (code "43") (name "Net-(U4-MCLK)") (class "Default")
      (node (ref "R2") (pin "1") (pintype "passive"))
      (node (ref "U4") (pin "16") (pinfunction "MCLK_16") (pintype "passive"))
    )
    (net (code "44") (name "Net-(U4-REFIN+{slash}OUT)") (class "Default")
      (node (ref "C11") (pin "1") (pintype "passive"))
      (node (ref "C12") (pin "1") (pintype "passive"))
      (node (ref "R28") (pin "2") (pintype "passive"))
      (node (ref "U4") (pin "2") (pinfunction "REFIN+/OUT_2") (pintype "passive"))
    )
    (net (code "45") (name "Net-(U4-SCK)") (class "Default")
      (node (ref "R9") (pin "1") (pintype "passive"))
      (node (ref "U4") (pin "12") (pinfunction "SCK_12") (pintype "passive"))
    )
    (net (code "46") (name "Net-(U4-SDI)") (class "Default")
      (node (ref "R6") (pin "1") (pintype "passive"))
      (node (ref "U4") (pin "13") (pinfunction "SDI_13") (pintype "passive"))
    )
    (net (code "47") (name "Net-(U4-SDO)") (class "Default")
      (node (ref "R5") (pin "1") (pintype "passive"))
      (node (ref "U4") (pin "14") (pinfunction "SDO_14") (pintype "passive"))
    )
    (net (code "48") (name "Net-(U4-~{CS})") (class "Default")
      (node (ref "R11") (pin "1") (pintype "passive"))
      (node (ref "U4") (pin "11") (pinfunction "~{CS}_11") (pintype "passive"))
    )
    (net (code "49") (name "Net-(U4-~{IRQ}{slash}MDAT)") (class "Default")
      (node (ref "R3") (pin "1") (pintype "passive"))
      (node (ref "U4") (pin "15") (pinfunction "~{IRQ}/MDAT_15") (pintype "passive"))
    )
    (net (code "50") (name "Net-(U5-+IN)") (class "Default")
      (node (ref "C14") (pin "2") (pintype "passive"))
      (node (ref "R26") (pin "1") (pintype "passive"))
      (node (ref "R27") (pin "2") (pintype "passive"))
      (node (ref "R7") (pin "1") (pintype "passive"))
      (node (ref "U5") (pin "8") (pinfunction "+IN_8") (pintype "passive"))
    )
    (net (code "51") (name "Net-(U5-+OUT)") (class "Default")
      (node (ref "C15") (pin "1") (pintype "passive"))
      (node (ref "R10") (pin "1") (pintype "passive"))
      (node (ref "R8") (pin "2") (pintype "passive"))
      (node (ref "U5") (pin "4") (pinfunction "+OUT_4") (pintype "passive"))
    )
    (net (code "52") (name "Net-(U5--IN)") (class "Default")
      (node (ref "C15") (pin "2") (pintype "passive"))
      (node (ref "J4") (pin "1") (pintype "passive"))
      (node (ref "R8") (pin "1") (pintype "passive"))
      (node (ref "U5") (pin "1") (pinfunction "-IN_1") (pintype "passive"))
    )
    (net (code "53") (name "Net-(U5--OUT)") (class "Default")
      (node (ref "C14") (pin "1") (pintype "passive"))
      (node (ref "R4") (pin "1") (pintype "passive"))
      (node (ref "R7") (pin "2") (pintype "passive"))
      (node (ref "U5") (pin "5") (pinfunction "-OUT_5") (pintype "passive"))
    )
    (net (code "54") (name "Net-(U5--VS)") (class "Default")
      (node (ref "C13") (pin "1") (pintype "passive"))
      (node (ref "U5") (pin "6") (pinfunction "-VS_6") (pintype "passive"))
    )
    (net (code "55") (name "Net-(U5-VMID)") (class "Default")
      (node (ref "C17") (pin "1") (pintype "passive"))
      (node (ref "U5") (pin "2") (pinfunction "VOCM_2") (pintype "passive"))
      (node (ref "U5") (pin "7") (pinfunction "VMID_7") (pintype "passive"))
    )
    (net (code "56") (name "Net-(U6-SCL)") (class "Default")
      (node (ref "J3") (pin "6") (pintype "passive"))
      (node (ref "R13") (pin "1") (pintype "passive"))
      (node (ref "U6") (pin "12") (pinfunction "SCL_12") (pintype "passive"))
    )
    (net (code "57") (name "Net-(U6-SDA)") (class "Default")
      (node (ref "J3") (pin "5") (pintype "passive"))
      (node (ref "R12") (pin "1") (pintype "passive"))
      (node (ref "U6") (pin "13") (pinfunction "SDA_13") (pintype "passive"))
    )
    (net (code "58") (name "unconnected-(J1-Pad2)") (class "Default")
      (node (ref "J1") (pin "2") (pintype "passive"))
    )
    (net (code "59") (name "unconnected-(J1-Pad4)") (class "Default")
      (node (ref "J1") (pin "4") (pintype "passive"))
    )
    (net (code "60") (name "unconnected-(J1-Pad10)") (class "Default")
      (node (ref "J1") (pin "10") (pintype "passive"))
    )
    (net (code "61") (name "unconnected-(J1-Pad12)") (class "Default")
      (node (ref "J1") (pin "12") (pintype "passive"))
    )
    (net (code "62") (name "unconnected-(J1-Pad14)") (class "Default")
      (node (ref "J1") (pin "14") (pintype "passive"))
    )
    (net (code "63") (name "unconnected-(J2-Pad2)") (class "Default")
      (node (ref "J2") (pin "2") (pintype "passive"))
    )
    (net (code "64") (name "unconnected-(J2-Pad4)") (class "Default")
      (node (ref "J2") (pin "4") (pintype "passive"))
    )
    (net (code "65") (name "unconnected-(J2-Pad10)") (class "Default")
      (node (ref "J2") (pin "10") (pintype "passive"))
    )
    (net (code "66") (name "unconnected-(J2-Pad12)") (class "Default")
      (node (ref "J2") (pin "12") (pintype "passive"))
    )
    (net (code "67") (name "unconnected-(J2-Pad14)") (class "Default")
      (node (ref "J2") (pin "14") (pintype "passive"))
    )
    (net (code "68") (name "unconnected-(J3-Pad14)") (class "Default")
      (node (ref "J3") (pin "14") (pintype "passive"))
    )
    (net (code "69") (name "unconnected-(U2-2IN+-Pad5)") (class "Default")
      (node (ref "U2") (pin "5") (pinfunction "2IN+_5") (pintype "passive+no_connect"))
    )
    (net (code "70") (name "unconnected-(U2-2IN--Pad6)") (class "Default")
      (node (ref "U2") (pin "6") (pinfunction "2IN-_6") (pintype "passive+no_connect"))
    )
    (net (code "71") (name "unconnected-(U2-2OUT-Pad7)") (class "Default")
      (node (ref "U2") (pin "7") (pinfunction "2OUT_7") (pintype "passive+no_connect"))
    )
    (net (code "72") (name "unconnected-(U3-NC-Pad2)") (class "Default")
      (node (ref "U3") (pin "2") (pinfunction "NC_2") (pintype "passive+no_connect"))
    )
    (net (code "73") (name "unconnected-(U4-NC_1-Pad5)") (class "Default")
      (node (ref "U4") (pin "5") (pinfunction "NC_1_5") (pintype "passive+no_connect"))
    )
    (net (code "74") (name "unconnected-(U4-NC_2-Pad6)") (class "Default")
      (node (ref "U4") (pin "6") (pinfunction "NC_2_6") (pintype "passive+no_connect"))
    )
    (net (code "75") (name "unconnected-(U4-NC_3-Pad7)") (class "Default")
      (node (ref "U4") (pin "7") (pinfunction "NC_3_7") (pintype "passive+no_connect"))
    )
    (net (code "76") (name "unconnected-(U4-NC_4-Pad8)") (class "Default")
      (node (ref "U4") (pin "8") (pinfunction "NC_4_8") (pintype "passive+no_connect"))
    )
    (net (code "77") (name "unconnected-(U4-NC_5-Pad9)") (class "Default")
      (node (ref "U4") (pin "9") (pinfunction "NC_5_9") (pintype "passive+no_connect"))
    )
    (net (code "78") (name "unconnected-(U4-NC_6-Pad10)") (class "Default")
      (node (ref "U4") (pin "10") (pinfunction "NC_6_10") (pintype "passive+no_connect"))
    )
    (net (code "79") (name "unconnected-(U6-SC2-Pad8)") (class "Default")
      (node (ref "U6") (pin "8") (pinfunction "SC2_8") (pintype "passive+no_connect"))
    )
    (net (code "80") (name "unconnected-(U6-SC3-Pad10)") (class "Default")
      (node (ref "U6") (pin "10") (pinfunction "SC3_10") (pintype "passive+no_connect"))
    )
    (net (code "81") (name "unconnected-(U6-SD2-Pad7)") (class "Default")
      (node (ref "U6") (pin "7") (pinfunction "SD2_7") (pintype "passive+no_connect"))
    )
    (net (code "82") (name "unconnected-(U6-SD3-Pad9)") (class "Default")
      (node (ref "U6") (pin "9") (pinfunction "SD3_9") (pintype "passive+no_connect"))
    )
  )
)
